# RF_Frontend_2.net
KiCad netlist of a schematic drawn in Altium Designer
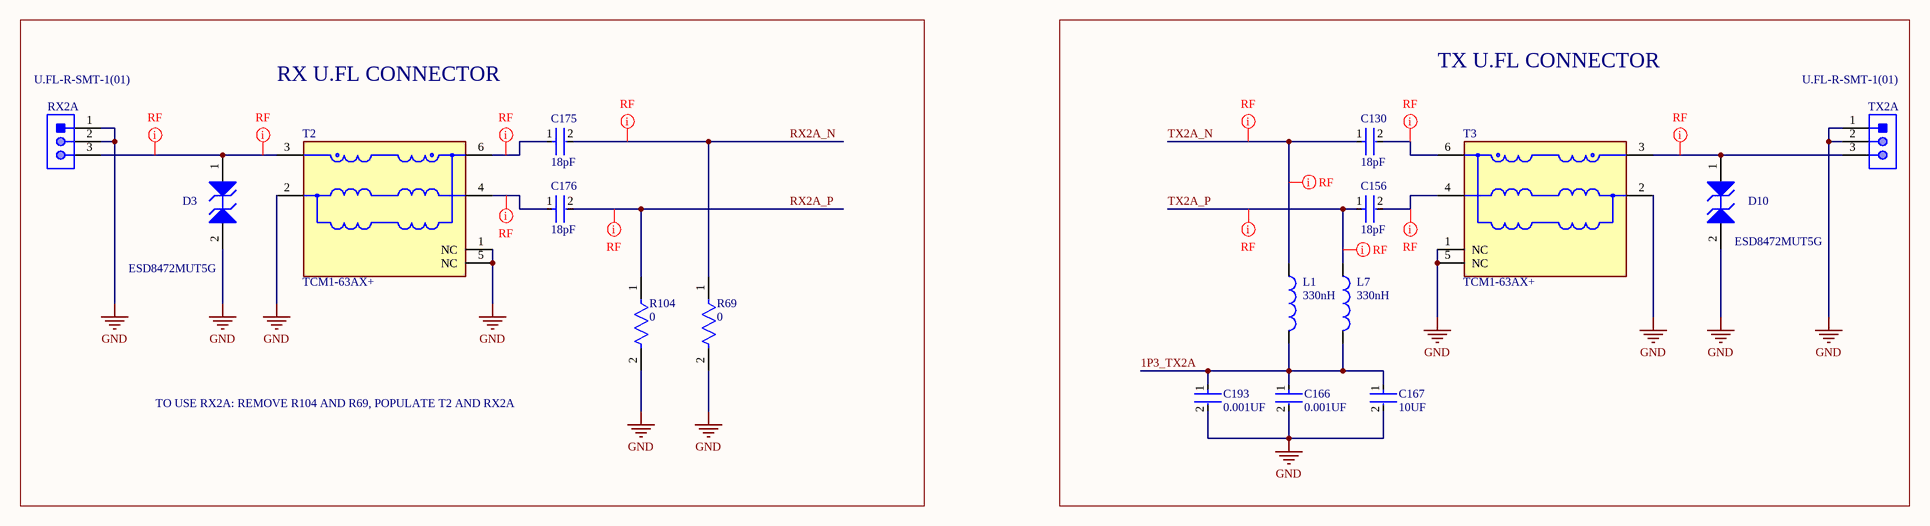
[diagram p0: RF Frontend 2.SchDoc]

(export (version "E")
  (design (tool "Eeschema 10.0.6"))
  (components
    (comp (ref "C130")
      (value "18pF")
      (footprint "FP-GRM033-0_03-IPC_A")
      (description "Chip Multilayer Ceramic Capacitors for General Purpose, 0201, 18pF, C0G, 30ppm/°C, 5%, 50V")
      (fields (field (name "TOLERANCE") "5%") (field (name "VOLTAGE") "50V"))
      (libsource (lib "Altium Content Vault") (part "b4654b650e69147ec39a6b967a45e02"))
    )
    (comp (ref "C156")
      (value "18pF")
      (footprint "FP-GRM033-0_03-IPC_A")
      (description "Chip Multilayer Ceramic Capacitors for General Purpose, 0201, 18pF, C0G, 30ppm/°C, 5%, 50V")
      (fields (field (name "TOLERANCE") "5%") (field (name "VOLTAGE") "50V"))
      (libsource (lib "Altium Content Vault") (part "b4654b650e69147ec39a6b967a45e02"))
    )
    (comp (ref "C166")
      (value "0.001UF")
      (footprint "FP-GRM033-0_03-MFG")
      (description "Chip Multilayer Ceramic Capacitors for General Purpose, 0201, 1000pF, X7R, 15%, 10%, 25V")
      (fields (field (name "TOLERANCE") "10%") (field (name "VOLTAGE") "25V"))
      (libsource (lib "Altium Content Vault") (part "b4654b650e69147ec39a6b967a45e02"))
    )
    (comp (ref "C167")
      (value "10UF")
      (footprint "FP-GRM188-0_1-e0_2_0_55-IPC_A")
      (description "Chip Multilayer Ceramic Capacitors for General Purpose, 0603, 10uF, X5R, 15%, 20%, 6.3V")
      (fields (field (name "VOLTAGE") "6.3V") (field (name "TOLERANCE") "20%"))
      (libsource (lib "Altium Content Vault") (part "02cd4be3c70576c341d710602a673aa"))
    )
    (comp (ref "C175")
      (value "18pF")
      (footprint "FP-GRM033-0_03-IPC_A")
      (description "Chip Multilayer Ceramic Capacitors for General Purpose, 0201, 18pF, C0G, 30ppm/°C, 5%, 50V")
      (fields (field (name "TOLERANCE") "5%") (field (name "VOLTAGE") "50V"))
      (libsource (lib "Altium Content Vault") (part "b4654b650e69147ec39a6b967a45e02"))
    )
    (comp (ref "C176")
      (value "18pF")
      (footprint "FP-GRM033-0_03-IPC_A")
      (description "Chip Multilayer Ceramic Capacitors for General Purpose, 0201, 18pF, C0G, 30ppm/°C, 5%, 50V")
      (fields (field (name "TOLERANCE") "5%") (field (name "VOLTAGE") "50V"))
      (libsource (lib "Altium Content Vault") (part "b4654b650e69147ec39a6b967a45e02"))
    )
    (comp (ref "C193")
      (value "0.001UF")
      (footprint "FP-GRM033-0_03-MFG")
      (description "Chip Multilayer Ceramic Capacitors for General Purpose, 0201, 1000pF, X7R, 15%, 10%, 25V")
      (fields (field (name "TOLERANCE") "10%") (field (name "VOLTAGE") "25V"))
      (libsource (lib "Altium Content Vault") (part "b4654b650e69147ec39a6b967a45e02"))
    )
    (comp (ref "D3")
      (value "ESD8472MUT5G")
      (footprint "ONSC-X3DFN-2-152AF-01_V")
      (fields (field (name "MANUFACTURER") "On Semiconductor"))
      (libsource (lib "Altium Content Vault") (part "ONSC-A1A2-2"))
    )
    (comp (ref "D10")
      (value "ESD8472MUT5G")
      (footprint "ONSC-X3DFN-2-152AF-01_V")
      (fields (field (name "MANUFACTURER") "On Semiconductor"))
      (libsource (lib "Altium Content Vault") (part "ONSC-A1A2-2"))
    )
    (comp (ref "L1")
      (value "330nH")
      (footprint "0402-A")
      (description "Inductor")
      (fields (field (name "PUBLISHER") "Altium Limited"))
      (libsource (lib "Miscellaneous Devices") (part "Inductor"))
    )
    (comp (ref "L7")
      (value "330nH")
      (footprint "0402-A")
      (description "Inductor")
      (fields (field (name "PUBLISHER") "Altium Limited"))
      (libsource (lib "Miscellaneous Devices") (part "Inductor"))
    )
    (comp (ref "R69")
      (value "0")
      (footprint "FP-ERJ1GN-IPC_A")
      (description "RES SMD 0 OHM JUMPER 1/20W 0201")
      (fields (field (name "TOLERANCE") "1%"))
      (libsource (lib "Altium Content Vault") (part "1029c3af85768c4190bb7ad29bc67b5"))
    )
    (comp (ref "R104")
      (value "0")
      (footprint "FP-ERJ1GN-IPC_A")
      (description "RES SMD 0 OHM JUMPER 1/20W 0201")
      (fields (field (name "TOLERANCE") "1%"))
      (libsource (lib "Altium Content Vault") (part "1029c3af85768c4190bb7ad29bc67b5"))
    )
    (comp (ref "RX2A")
      (value "U.FL-R-SMT-1(01)")
      (footprint "HRS-U.FL-R-SMT-3_V")
      (description "Ultra Small Coaxial Connector, 6 GHz, -40 to 90 degC, 3-Pin SMD, RoHS, Bulk")
      (fields (field (name "MANUFACTURER") "Hirose Electric"))
      (libsource (lib "") (part "CN-1P-M-R3_1"))
    )
    (comp (ref "T2")
      (value "TCM1-63AX+")
      (footprint "FP-TCM1-63AX+-MFG")
      (description "1:1 CORE & WIRE Transformer, 10 - 6000 MHz, 50Ω")
      (fields
        (field (name "MANUFACTURER") "Mini-Circuits")
        (field (name "OCTOPART") "https://octopart.com/tcm1-63ax%2B-mini-circuits-107315723")
      )
      (libsource (lib "Altium Content Vault") (part "572340aedd709dbafee1a1d3331a406"))
    )
    (comp (ref "T3")
      (value "TCM1-63AX+")
      (footprint "FP-TCM1-63AX+-MFG")
      (description "1:1 CORE & WIRE Transformer, 10 - 6000 MHz, 50Ω")
      (fields
        (field (name "MANUFACTURER") "Mini-Circuits")
        (field (name "OCTOPART") "https://octopart.com/tcm1-63ax%2B-mini-circuits-107315723")
      )
      (libsource (lib "") (part "572340aedd709dbafee1a1d3331a406_1"))
    )
    (comp (ref "TX2A")
      (value "U.FL-R-SMT-1(01)")
      (footprint "HRS-U.FL-R-SMT-3_V")
      (description "Ultra Small Coaxial Connector, 6 GHz, -40 to 90 degC, 3-Pin SMD, RoHS, Bulk")
      (fields (field (name "MANUFACTURER") "Hirose Electric"))
      (libsource (lib "Altium Content Vault") (part "CN-1P-M-R3"))
    )
  )
  (nets
    (net (code "1") (name "/1P3_TX2A") (class "Default")
      (node (ref "C166") (pin "1") (pinfunction "1_1") (pintype "passive"))
      (node (ref "C167") (pin "1") (pinfunction "1_1") (pintype "passive"))
      (node (ref "C193") (pin "1") (pinfunction "1_1") (pintype "passive"))
      (node (ref "L1") (pin "2") (pinfunction "2_2") (pintype "passive"))
      (node (ref "L7") (pin "2") (pinfunction "2_2") (pintype "passive"))
    )
    (net (code "2") (name "/RX2A_N") (class "Default")
      (node (ref "C175") (pin "2") (pinfunction "2_2") (pintype "passive"))
      (node (ref "R69") (pin "1") (pinfunction "1_1") (pintype "passive"))
    )
    (net (code "3") (name "/RX2A_P") (class "Default")
      (node (ref "C176") (pin "2") (pinfunction "2_2") (pintype "passive"))
      (node (ref "R104") (pin "1") (pinfunction "1_1") (pintype "passive"))
    )
    (net (code "4") (name "/TX2A_N") (class "Default")
      (node (ref "C130") (pin "1") (pinfunction "1_1") (pintype "passive"))
      (node (ref "L1") (pin "1") (pinfunction "1_1") (pintype "passive"))
    )
    (net (code "5") (name "/TX2A_P") (class "Default")
      (node (ref "C156") (pin "1") (pinfunction "1_1") (pintype "passive"))
      (node (ref "L7") (pin "1") (pinfunction "1_1") (pintype "passive"))
    )
    (net (code "6") (name "GND") (class "Default")
      (node (ref "C166") (pin "2") (pinfunction "2_2") (pintype "passive"))
      (node (ref "C167") (pin "2") (pinfunction "2_2") (pintype "passive"))
      (node (ref "C193") (pin "2") (pinfunction "2_2") (pintype "passive"))
      (node (ref "D10") (pin "2") (pinfunction "A2_2") (pintype "passive"))
      (node (ref "D3") (pin "2") (pinfunction "A2_2") (pintype "passive"))
      (node (ref "R104") (pin "2") (pinfunction "2_2") (pintype "passive"))
      (node (ref "R69") (pin "2") (pinfunction "2_2") (pintype "passive"))
      (node (ref "RX2A") (pin "1") (pinfunction "1_1") (pintype "passive"))
      (node (ref "RX2A") (pin "2") (pinfunction "2_2") (pintype "passive"))
      (node (ref "T2") (pin "1") (pinfunction "NC_1") (pintype "passive"))
      (node (ref "T2") (pin "2") (pinfunction "GND_2") (pintype "passive"))
      (node (ref "T2") (pin "5") (pinfunction "NC_5") (pintype "passive"))
      (node (ref "T3") (pin "1") (pinfunction "NC_1") (pintype "passive"))
      (node (ref "T3") (pin "2") (pinfunction "GND_2") (pintype "passive"))
      (node (ref "T3") (pin "5") (pinfunction "NC_5") (pintype "passive"))
      (node (ref "TX2A") (pin "1") (pinfunction "1_1") (pintype "passive"))
      (node (ref "TX2A") (pin "2") (pinfunction "2_2") (pintype "passive"))
    )
    (net (code "7") (name "Net-(D3-A1)") (class "Default")
      (node (ref "D3") (pin "1") (pinfunction "A1_1") (pintype "passive"))
      (node (ref "RX2A") (pin "3") (pinfunction "3_3") (pintype "passive"))
      (node (ref "T2") (pin "3") (pinfunction "PRIMARY_DOT_3") (pintype "passive"))
    )
    (net (code "8") (name "Net-(D10-A1)") (class "Default")
      (node (ref "D10") (pin "1") (pinfunction "A1_1") (pintype "passive"))
      (node (ref "T3") (pin "3") (pinfunction "PRIMARY_DOT_3") (pintype "passive"))
      (node (ref "TX2A") (pin "3") (pinfunction "3_3") (pintype "passive"))
    )
    (net (code "9") (name "Net-(T2-SECONDARY)") (class "Default")
      (node (ref "C176") (pin "1") (pinfunction "1_1") (pintype "passive"))
      (node (ref "T2") (pin "4") (pinfunction "SECONDARY_4") (pintype "passive"))
    )
    (net (code "10") (name "Net-(T2-SECONDARY_DOT)") (class "Default")
      (node (ref "C175") (pin "1") (pinfunction "1_1") (pintype "passive"))
      (node (ref "T2") (pin "6") (pinfunction "SECONDARY_DOT_6") (pintype "passive"))
    )
    (net (code "11") (name "Net-(T3-SECONDARY)") (class "Default")
      (node (ref "C156") (pin "2") (pinfunction "2_2") (pintype "passive"))
      (node (ref "T3") (pin "4") (pinfunction "SECONDARY_4") (pintype "passive"))
    )
    (net (code "12") (name "Net-(T3-SECONDARY_DOT)") (class "Default")
      (node (ref "C130") (pin "2") (pinfunction "2_2") (pintype "passive"))
      (node (ref "T3") (pin "6") (pinfunction "SECONDARY_DOT_6") (pintype "passive"))
    )
  )
)
